# PX4FMUv2_4_6_06.net
KiCad netlist of a schematic drawn in Altium Designer
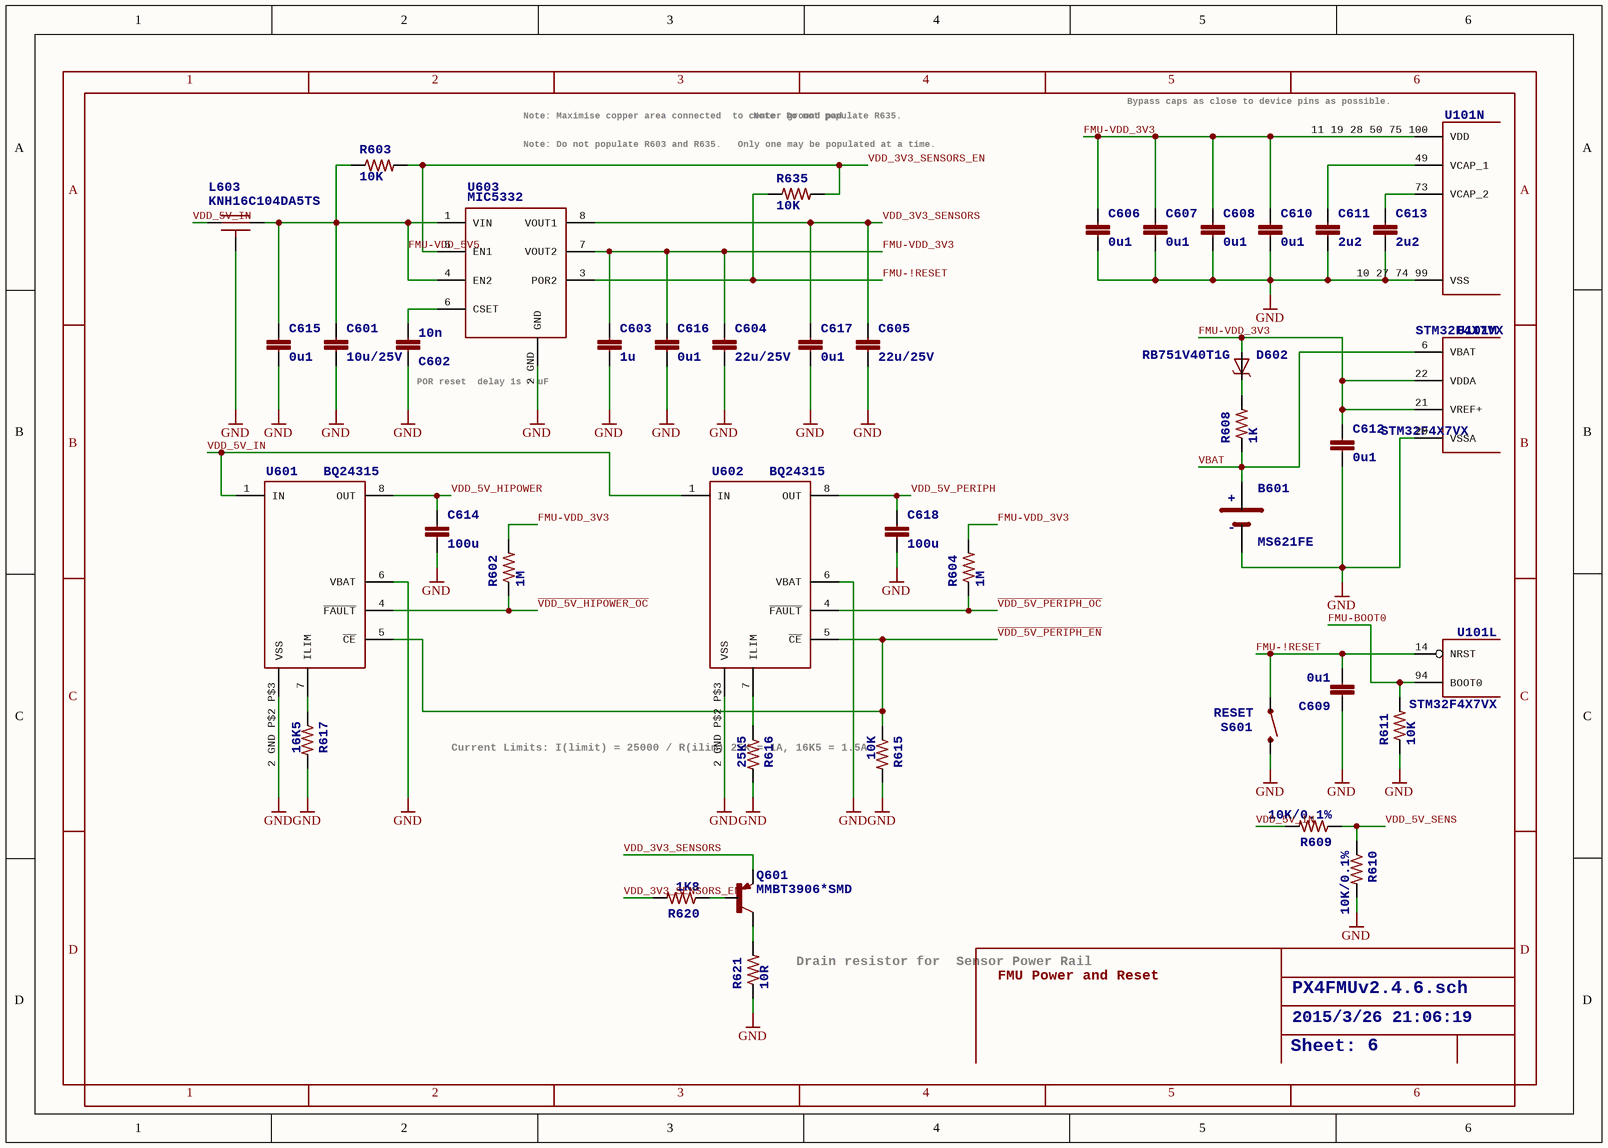
[diagram p0: PX4FMUv2.4.6_06.SchDoc]

(export (version "E")
  (design (tool "Eeschema 10.0.6"))
  (components
    (comp (ref "B601")
      (value "MS621FE")
      (footprint "MS621FE")
      (fields (field (name "PARTNO") "MS621FE-FL11E") (field (name "+") "+") (field (name "-") "-"))
      (libsource (lib "pixhawk2") (part "MS621FE"))
    )
    (comp (ref "C601")
      (value "10u/25V")
      (footprint "0805-CAP")
      (description "<b>Capacitor</b>\nStandard 0603 ceramic capacitor, and 0.1\" leaded capacitor.")
      (fields (field (name "PARTNO") "CL21A106KAYNNNE"))
      (libsource (lib "pixhawk2") (part "CAP0805"))
    )
    (comp (ref "C602")
      (value "10n")
      (footprint "0402-CAP")
      (description "<b>Capacitor</b>\nStandard 0603 ceramic capacitor, and 0.1\" leaded capacitor.")
      (fields (field (name "PARTNO") "CC0402KRX7R7BB103"))
      (libsource (lib "") (part "CAP0402_2"))
    )
    (comp (ref "C603")
      (value "1u")
      (footprint "0603-CAP")
      (description "<b>Capacitor</b>\nStandard 0603 ceramic capacitor, and 0.1\" leaded capacitor.")
      (fields (field (name "PARTNO") "CC0603ZRY5V7BB105"))
      (libsource (lib "pixhawk2") (part "CAP0603"))
    )
    (comp (ref "C604")
      (value "22u/25V")
      (footprint "0805-CAP")
      (description "<b>Capacitor</b>\nStandard 0603 ceramic capacitor, and 0.1\" leaded capacitor.")
      (fields (field (name "PARTNO") "CL21A226MAQNNNE"))
      (libsource (lib "pixhawk2") (part "CAP0805"))
    )
    (comp (ref "C605")
      (value "22u/25V")
      (footprint "0805-CAP")
      (description "<b>Capacitor</b>\nStandard 0603 ceramic capacitor, and 0.1\" leaded capacitor.")
      (fields (field (name "PARTNO") "CL21A226MAQNNNE"))
      (libsource (lib "pixhawk2") (part "CAP0805"))
    )
    (comp (ref "C606")
      (value "0u1")
      (footprint "0402-CAP")
      (description "<b>Capacitor</b>\nStandard 0603 ceramic capacitor, and 0.1\" leaded capacitor.")
      (fields (field (name "PARTNO") "CC0402ZRY5V7BB104"))
      (libsource (lib "") (part "CAP0402_1"))
    )
    (comp (ref "C607")
      (value "0u1")
      (footprint "0402-CAP")
      (description "<b>Capacitor</b>\nStandard 0603 ceramic capacitor, and 0.1\" leaded capacitor.")
      (fields (field (name "PARTNO") "CC0402ZRY5V7BB104"))
      (libsource (lib "") (part "CAP0402_1"))
    )
    (comp (ref "C608")
      (value "0u1")
      (footprint "0402-CAP")
      (description "<b>Capacitor</b>\nStandard 0603 ceramic capacitor, and 0.1\" leaded capacitor.")
      (fields (field (name "PARTNO") "CC0402ZRY5V7BB104"))
      (libsource (lib "") (part "CAP0402_1"))
    )
    (comp (ref "C609")
      (value "0u1")
      (footprint "0402-CAP")
      (description "<b>Capacitor</b>\nStandard 0603 ceramic capacitor, and 0.1\" leaded capacitor.")
      (fields (field (name "PARTNO") "CC0402ZRY5V7BB104"))
      (libsource (lib "pixhawk2") (part "CAP0402"))
    )
    (comp (ref "C610")
      (value "0u1")
      (footprint "0402-CAP")
      (description "<b>Capacitor</b>\nStandard 0603 ceramic capacitor, and 0.1\" leaded capacitor.")
      (fields (field (name "PARTNO") "CC0402ZRY5V7BB104"))
      (libsource (lib "") (part "CAP0402_1"))
    )
    (comp (ref "C611")
      (value "2u2")
      (footprint "0603-CAP")
      (description "<b>Capacitor</b>\nStandard 0603 ceramic capacitor, and 0.1\" leaded capacitor.")
      (fields (field (name "PARTNO") "C1608X6S1C225K080AC"))
      (libsource (lib "pixhawk2") (part "CAP0603"))
    )
    (comp (ref "C612")
      (value "0u1")
      (footprint "0402-CAP")
      (description "<b>Capacitor</b>\nStandard 0603 ceramic capacitor, and 0.1\" leaded capacitor.")
      (fields (field (name "PARTNO") "CC0402ZRY5V7BB104"))
      (libsource (lib "") (part "CAP0402_1"))
    )
    (comp (ref "C613")
      (value "2u2")
      (footprint "0603-CAP")
      (description "<b>Capacitor</b>\nStandard 0603 ceramic capacitor, and 0.1\" leaded capacitor.")
      (fields (field (name "PARTNO") "C1608X6S1C225K080AC"))
      (libsource (lib "pixhawk2") (part "CAP0603"))
    )
    (comp (ref "C614")
      (value "100u")
      (footprint "1206-CAP")
      (description "<b>Capacitor</b>\nStandard 0603 ceramic capacitor, and 0.1\" leaded capacitor.")
      (fields (field (name "PARTNO") "C3216X5R1A107M160AC"))
      (libsource (lib "pixhawk2") (part "CAP1206"))
    )
    (comp (ref "C615")
      (value "0u1")
      (footprint "0402-CAP")
      (description "<b>Capacitor</b>\nStandard 0603 ceramic capacitor, and 0.1\" leaded capacitor.")
      (fields (field (name "PARTNO") "CC0402ZRY5V7BB104"))
      (libsource (lib "") (part "CAP0402_1"))
    )
    (comp (ref "C616")
      (value "0u1")
      (footprint "0402-CAP")
      (description "<b>Capacitor</b>\nStandard 0603 ceramic capacitor, and 0.1\" leaded capacitor.")
      (fields (field (name "PARTNO") "CC0402ZRY5V7BB104"))
      (libsource (lib "") (part "CAP0402_1"))
    )
    (comp (ref "C617")
      (value "0u1")
      (footprint "0402-CAP")
      (description "<b>Capacitor</b>\nStandard 0603 ceramic capacitor, and 0.1\" leaded capacitor.")
      (fields (field (name "PARTNO") "CC0402ZRY5V7BB104"))
      (libsource (lib "") (part "CAP0402_1"))
    )
    (comp (ref "C618")
      (value "100u")
      (footprint "1206-CAP")
      (description "<b>Capacitor</b>\nStandard 0603 ceramic capacitor, and 0.1\" leaded capacitor.")
      (fields (field (name "PARTNO") "C3216X5R1A107M160AC"))
      (libsource (lib "pixhawk2") (part "CAP1206"))
    )
    (comp (ref "D602")
      (value "RB751V40T1G")
      (footprint "SOD323")
      (description "Schottky barrier diode in DO214AC, e.g. Fairchild SS14.")
      (libsource (lib "pixhawk2") (part "DIODE-SCHOTTKY_SOD323"))
    )
    (comp (ref "L603")
      (value "KNH16C104DA5TS")
      (footprint "KYOCERA-KNH16-DA")
      (description "Kyocera KNH16C104DA5TS EMI filter")
      (libsource (lib "pixhawk2") (part "KNH16C104DA5TS"))
    )
    (comp (ref "Q601")
      (value "MMBT3906*SMD")
      (footprint "SOT23-BEC")
      (description "<b>PNP Transistror</b>")
      (libsource (lib "transistor-pnp") (part "MMBT3906*SMD"))
    )
    (comp (ref "R602")
      (value "1M")
      (footprint "0402-RES")
      (fields (field (name "PARTNO") "RC0402FR-071ML"))
      (libsource (lib "pixhawk2") (part "RESISTOR0402-RES"))
    )
    (comp (ref "R603")
      (value "10K")
      (footprint "0402-RES")
      (fields (field (name "PARTNO") "RC0402FR-0710KL"))
      (libsource (lib "pixhawk2") (part "RESISTOR0402-RES"))
    )
    (comp (ref "R604")
      (value "1M")
      (footprint "0402-RES")
      (fields (field (name "PARTNO") "RC0402FR-071ML"))
      (libsource (lib "pixhawk2") (part "RESISTOR0402-RES"))
    )
    (comp (ref "R608")
      (value "1K")
      (footprint "0402-RES")
      (fields (field (name "PARTNO") "RC0402FR-071KL"))
      (libsource (lib "pixhawk2") (part "RESISTOR0402-RES"))
    )
    (comp (ref "R609")
      (value "10K/0.1%")
      (footprint "0402-RES")
      (fields (field (name "PARTNO") "ERA-2AEB103X"))
      (libsource (lib "pixhawk2") (part "RESISTOR0402-RES"))
    )
    (comp (ref "R610")
      (value "10K/0.1%")
      (footprint "0402-RES")
      (fields (field (name "PARTNO") "ERA-2AEB103X"))
      (libsource (lib "pixhawk2") (part "RESISTOR0402-RES"))
    )
    (comp (ref "R611")
      (value "10K")
      (footprint "0402-RES")
      (fields (field (name "PARTNO") "RC0402FR-0710KL"))
      (libsource (lib "pixhawk2") (part "RESISTOR0402-RES"))
    )
    (comp (ref "R615")
      (value "10K")
      (footprint "0402-RES")
      (fields (field (name "PARTNO") "RC0402FR-0710KL"))
      (libsource (lib "pixhawk2") (part "RESISTOR0402-RES"))
    )
    (comp (ref "R616")
      (value "25K5")
      (footprint "0402-RES")
      (fields (field (name "PARTNO") "RMCF0402FT25K5"))
      (libsource (lib "pixhawk2") (part "RESISTOR0402-RES"))
    )
    (comp (ref "R617")
      (value "16K5")
      (footprint "0402-RES")
      (fields (field (name "PARTNO") "RMCF0402FT16K5"))
      (libsource (lib "pixhawk2") (part "RESISTOR0402-RES"))
    )
    (comp (ref "R620")
      (value "1K8")
      (footprint "0402-RES")
      (fields (field (name "PARTNO") "RC1005F182CS"))
      (libsource (lib "pixhawk2") (part "RESISTOR0402-RES"))
    )
    (comp (ref "R621")
      (value "10R")
      (footprint "0603-RES")
      (fields (field (name "PARTNO") "RC1608J100CS"))
      (libsource (lib "pixhawk2") (part "RESISTOR0603-RES"))
    )
    (comp (ref "R635")
      (value "10K")
      (footprint "0402-RES")
      (fields (field (name "PARTNO") "RC0402FR-0710KL"))
      (libsource (lib "pixhawk2") (part "RESISTOR0402-RES"))
    )
    (comp (ref "S601")
      (value "RESET")
      (footprint "EVQP7J01K")
      (libsource (lib "pixhawk2") (part "SWITCH-MOMENTARY-2"))
    )
    (comp (ref "U101")
      (value "STM32F4X7VX")
      (footprint "TQFP100")
      (fields (field (name "PARTNO") "STM32F427VI"))
      (libsource (lib "pixhawk2") (part "STM32F4X7VX"))
    )
    (comp (ref "U601")
      (value "BQ24315")
      (footprint "QFN8-DSG")
      (fields (field (name "PARTNO") "BQ24315DSGR"))
      (libsource (lib "pixhawk2") (part "BQ24315"))
    )
    (comp (ref "U602")
      (value "BQ24315")
      (footprint "QFN8-DSG")
      (fields (field (name "PARTNO") "BQ24315DSGR"))
      (libsource (lib "pixhawk2") (part "BQ24315"))
    )
    (comp (ref "U603")
      (value "MIC5332")
      (footprint "MLF-8-EPAD")
      (fields (field (name "PARTNO") "MIC5332-SSYMT"))
      (libsource (lib "pixhawk2") (part "MIC5332"))
    )
  )
  (nets
    (net (code "1") (name "/FMU-!RESET") (class "Default")
      (node (ref "C609") (pin "P$2") (pinfunction "2_P$2") (pintype "passive"))
      (node (ref "R635") (pin "P$1") (pinfunction "1_P$1") (pintype "passive"))
      (node (ref "S601") (pin "A1") (pinfunction "1_A1") (pintype "passive"))
      (node (ref "U101") (pin "14") (pinfunction "NRST_14") (pintype "passive"))
      (node (ref "U603") (pin "3") (pinfunction "POR2_3") (pintype "passive"))
    )
    (net (code "2") (name "/FMU-BOOT0") (class "Default")
      (node (ref "R611") (pin "P$2") (pinfunction "2_P$2") (pintype "passive"))
      (node (ref "U101") (pin "94") (pinfunction "BOOT0_94") (pintype "passive"))
    )
    (net (code "3") (name "/FMU-VDD_3V3") (class "Default")
      (node (ref "C603") (pin "P$1") (pinfunction "1_P$1") (pintype "passive"))
      (node (ref "C604") (pin "P$1") (pinfunction "1_P$1") (pintype "passive"))
      (node (ref "C606") (pin "P$1") (pinfunction "1_P$1") (pintype "passive"))
      (node (ref "C607") (pin "P$1") (pinfunction "1_P$1") (pintype "passive"))
      (node (ref "C608") (pin "P$1") (pinfunction "1_P$1") (pintype "passive"))
      (node (ref "C610") (pin "P$1") (pinfunction "1_P$1") (pintype "passive"))
      (node (ref "C612") (pin "P$1") (pinfunction "1_P$1") (pintype "passive"))
      (node (ref "C616") (pin "P$1") (pinfunction "1_P$1") (pintype "passive"))
      (node (ref "D602") (pin "A") (pinfunction "A_A") (pintype "passive"))
      (node (ref "R602") (pin "P$2") (pinfunction "2_P$2") (pintype "passive"))
      (node (ref "R604") (pin "P$2") (pinfunction "2_P$2") (pintype "passive"))
      (node (ref "U101") (pin "11_19_28_50_75_100") (pinfunction "VDD_11_19_28_50_75_100") (pintype "power_in"))
      (node (ref "U101") (pin "21") (pinfunction "VREF+_21") (pintype "passive"))
      (node (ref "U101") (pin "22") (pinfunction "VDDA_22") (pintype "power_in"))
      (node (ref "U603") (pin "7") (pinfunction "VOUT2_7") (pintype "passive"))
    )
    (net (code "4") (name "/FMU-VDD_5V5") (class "Default")
      (node (ref "C601") (pin "P$1") (pinfunction "1_P$1") (pintype "passive"))
      (node (ref "C615") (pin "P$1") (pinfunction "1_P$1") (pintype "passive"))
      (node (ref "L603") (pin "P$2") (pinfunction "P$2_P$2") (pintype "passive"))
      (node (ref "R603") (pin "P$1") (pinfunction "1_P$1") (pintype "passive"))
      (node (ref "U603") (pin "1") (pinfunction "VIN_1") (pintype "passive"))
      (node (ref "U603") (pin "4") (pinfunction "EN2_4") (pintype "passive"))
    )
    (net (code "5") (name "/VBAT") (class "Default")
      (node (ref "B601") (pin "1") (pinfunction "POS_1") (pintype "passive"))
      (node (ref "R608") (pin "P$1") (pinfunction "1_P$1") (pintype "passive"))
      (node (ref "U101") (pin "6") (pinfunction "VBAT_6") (pintype "power_in"))
    )
    (net (code "6") (name "/VDD_3V3_SENSORS") (class "Default")
      (node (ref "C605") (pin "P$1") (pinfunction "1_P$1") (pintype "passive"))
      (node (ref "C617") (pin "P$1") (pinfunction "1_P$1") (pintype "passive"))
      (node (ref "Q601") (pin "E") (pinfunction "E_E") (pintype "passive"))
      (node (ref "U603") (pin "8") (pinfunction "VOUT1_8") (pintype "passive"))
    )
    (net (code "7") (name "/VDD_3V3_SENSORS_EN") (class "Default")
      (node (ref "R603") (pin "P$2") (pinfunction "2_P$2") (pintype "passive"))
      (node (ref "R620") (pin "P$2") (pinfunction "2_P$2") (pintype "passive"))
      (node (ref "R635") (pin "P$2") (pinfunction "2_P$2") (pintype "passive"))
      (node (ref "U603") (pin "5") (pinfunction "EN1_5") (pintype "passive"))
    )
    (net (code "8") (name "/VDD_5V_HIPOWER") (class "Default")
      (node (ref "C614") (pin "P$1") (pinfunction "1_P$1") (pintype "passive"))
      (node (ref "U601") (pin "8") (pinfunction "OUT_8") (pintype "passive"))
    )
    (net (code "9") (name "/VDD_5V_IN") (class "Default")
      (node (ref "L603") (pin "P$1") (pinfunction "P$1_P$1") (pintype "passive"))
      (node (ref "R609") (pin "P$2") (pinfunction "2_P$2") (pintype "passive"))
      (node (ref "U601") (pin "1") (pinfunction "IN_1") (pintype "passive"))
      (node (ref "U602") (pin "1") (pinfunction "IN_1") (pintype "passive"))
    )
    (net (code "10") (name "/VDD_5V_PERIPH") (class "Default")
      (node (ref "C618") (pin "P$1") (pinfunction "1_P$1") (pintype "passive"))
      (node (ref "U602") (pin "8") (pinfunction "OUT_8") (pintype "passive"))
    )
    (net (code "11") (name "/VDD_5V_SENS") (class "Default")
      (node (ref "R609") (pin "P$1") (pinfunction "1_P$1") (pintype "passive"))
      (node (ref "R610") (pin "P$1") (pinfunction "1_P$1") (pintype "passive"))
    )
    (net (code "12") (name "/~{VDD_5V_HIPOWER_OC}") (class "Default")
      (node (ref "R602") (pin "P$1") (pinfunction "1_P$1") (pintype "passive"))
      (node (ref "U601") (pin "4") (pinfunction "~{FAULT}_4") (pintype "passive"))
    )
    (net (code "13") (name "/~{VDD_5V_PERIPH_EN}") (class "Default")
      (node (ref "R615") (pin "P$1") (pinfunction "1_P$1") (pintype "passive"))
      (node (ref "U601") (pin "5") (pinfunction "~{CE}_5") (pintype "passive"))
      (node (ref "U602") (pin "5") (pinfunction "~{CE}_5") (pintype "passive"))
    )
    (net (code "14") (name "/~{VDD_5V_PERIPH_OC}") (class "Default")
      (node (ref "R604") (pin "P$1") (pinfunction "1_P$1") (pintype "passive"))
      (node (ref "U602") (pin "4") (pinfunction "~{FAULT}_4") (pintype "passive"))
    )
    (net (code "15") (name "GND") (class "Default")
      (node (ref "B601") (pin "2") (pinfunction "NEG_2") (pintype "passive"))
      (node (ref "C601") (pin "P$2") (pinfunction "2_P$2") (pintype "passive"))
      (node (ref "C602") (pin "P$1") (pinfunction "1_P$1") (pintype "passive"))
      (node (ref "C603") (pin "P$2") (pinfunction "2_P$2") (pintype "passive"))
      (node (ref "C604") (pin "P$2") (pinfunction "2_P$2") (pintype "passive"))
      (node (ref "C605") (pin "P$2") (pinfunction "2_P$2") (pintype "passive"))
      (node (ref "C606") (pin "P$2") (pinfunction "2_P$2") (pintype "passive"))
      (node (ref "C607") (pin "P$2") (pinfunction "2_P$2") (pintype "passive"))
      (node (ref "C608") (pin "P$2") (pinfunction "2_P$2") (pintype "passive"))
      (node (ref "C609") (pin "P$1") (pinfunction "1_P$1") (pintype "passive"))
      (node (ref "C610") (pin "P$2") (pinfunction "2_P$2") (pintype "passive"))
      (node (ref "C611") (pin "P$2") (pinfunction "2_P$2") (pintype "passive"))
      (node (ref "C612") (pin "P$2") (pinfunction "2_P$2") (pintype "passive"))
      (node (ref "C613") (pin "P$2") (pinfunction "2_P$2") (pintype "passive"))
      (node (ref "C614") (pin "P$2") (pinfunction "2_P$2") (pintype "passive"))
      (node (ref "C615") (pin "P$2") (pinfunction "2_P$2") (pintype "passive"))
      (node (ref "C616") (pin "P$2") (pinfunction "2_P$2") (pintype "passive"))
      (node (ref "C617") (pin "P$2") (pinfunction "2_P$2") (pintype "passive"))
      (node (ref "C618") (pin "P$2") (pinfunction "2_P$2") (pintype "passive"))
      (node (ref "L603") (pin "P$3_P$4_P$5") (pinfunction "P$3_P$3_P$4_P$5") (pintype "passive"))
      (node (ref "R610") (pin "P$2") (pinfunction "2_P$2") (pintype "passive"))
      (node (ref "R611") (pin "P$1") (pinfunction "1_P$1") (pintype "passive"))
      (node (ref "R615") (pin "P$2") (pinfunction "2_P$2") (pintype "passive"))
      (node (ref "R616") (pin "P$2") (pinfunction "2_P$2") (pintype "passive"))
      (node (ref "R617") (pin "P$2") (pinfunction "2_P$2") (pintype "passive"))
      (node (ref "R621") (pin "1") (pinfunction "1_1") (pintype "passive"))
      (node (ref "S601") (pin "B3") (pinfunction "2_B3") (pintype "passive"))
      (node (ref "U101") (pin "10_27_74_99") (pinfunction "VSS_10_27_74_99") (pintype "power_in"))
      (node (ref "U101") (pin "20") (pinfunction "VSSA_20") (pintype "power_in"))
      (node (ref "U601") (pin "2_GND_P$2_P$3") (pinfunction "VSS_2_GND_P$2_P$3") (pintype "passive"))
      (node (ref "U601") (pin "6") (pinfunction "VBAT_6") (pintype "passive"))
      (node (ref "U602") (pin "2_GND_P$2_P$3") (pinfunction "VSS_2_GND_P$2_P$3") (pintype "passive"))
      (node (ref "U602") (pin "6") (pinfunction "VBAT_6") (pintype "passive"))
      (node (ref "U603") (pin "2_GND") (pinfunction "GND_2_GND") (pintype "passive"))
    )
    (net (code "16") (name "Net-(C602-2)") (class "Default")
      (node (ref "C602") (pin "P$2") (pinfunction "2_P$2") (pintype "passive"))
      (node (ref "U603") (pin "6") (pinfunction "CSET_6") (pintype "passive"))
    )
    (net (code "17") (name "Net-(C611-1)") (class "Default")
      (node (ref "C611") (pin "P$1") (pinfunction "1_P$1") (pintype "passive"))
      (node (ref "U101") (pin "49") (pinfunction "VCAP_1_49") (pintype "power_in"))
    )
    (net (code "18") (name "Net-(C613-1)") (class "Default")
      (node (ref "C613") (pin "P$1") (pinfunction "1_P$1") (pintype "passive"))
      (node (ref "U101") (pin "73") (pinfunction "VCAP_2_73") (pintype "power_in"))
    )
    (net (code "19") (name "Net-(Q601-PadC)") (class "Default")
      (node (ref "Q601") (pin "C") (pinfunction "C_C") (pintype "passive"))
      (node (ref "R621") (pin "2") (pinfunction "2_2") (pintype "passive"))
    )
    (net (code "20") (name "Net-(R608-2)") (class "Default")
      (node (ref "D602") (pin "C") (pinfunction "C_C") (pintype "passive"))
      (node (ref "R608") (pin "P$2") (pinfunction "2_P$2") (pintype "passive"))
    )
    (net (code "21") (name "Net-(R616-1)") (class "Default")
      (node (ref "R616") (pin "P$1") (pinfunction "1_P$1") (pintype "passive"))
      (node (ref "U602") (pin "7") (pinfunction "ILIM_7") (pintype "passive"))
    )
    (net (code "22") (name "Net-(R617-1)") (class "Default")
      (node (ref "R617") (pin "P$1") (pinfunction "1_P$1") (pintype "passive"))
      (node (ref "U601") (pin "7") (pinfunction "ILIM_7") (pintype "passive"))
    )
    (net (code "23") (name "Net-(R620-1)") (class "Default")
      (node (ref "Q601") (pin "B") (pinfunction "B_B") (pintype "passive"))
      (node (ref "R620") (pin "P$1") (pinfunction "1_P$1") (pintype "passive"))
    )
  )
)
